# MAX6682_Breakout.net
KiCad netlist of a schematic drawn in EAGLE
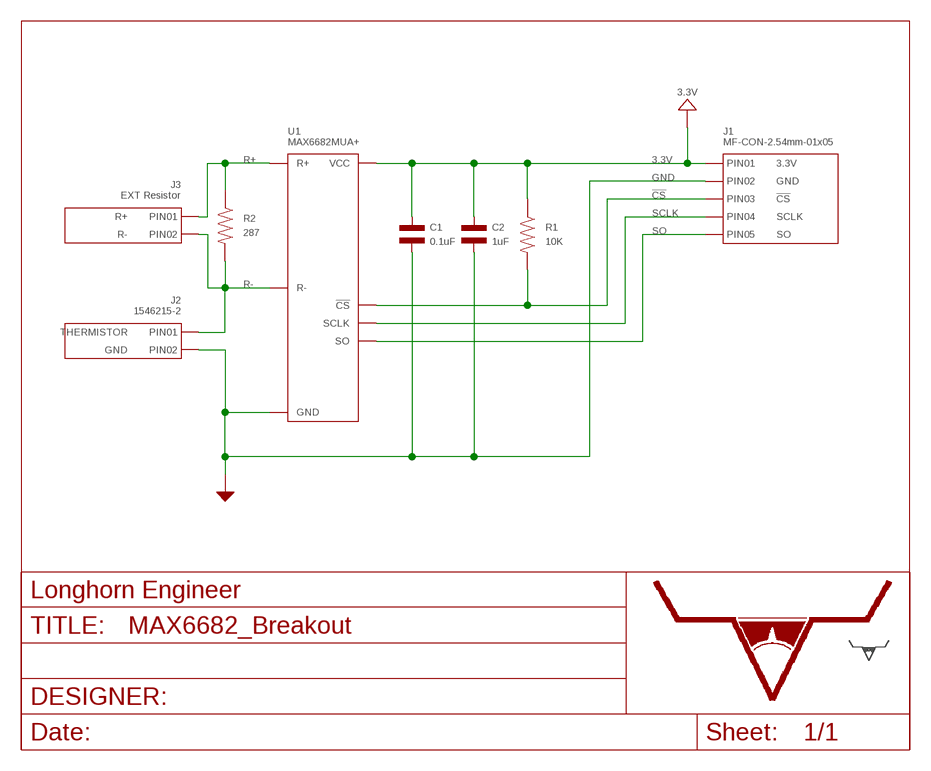
[diagram p0: schematic, sheet 1]

(export (version "E")
  (design (tool "Eeschema 10.0.6"))
  (components
    (comp (ref "C1")
      (value "0.1uF")
      (footprint "eagle-import:C0603")
      (libsource (lib "eagle-import") (part "CAPACITOR_NP_0603"))
    )
    (comp (ref "C2")
      (value "1uF")
      (footprint "eagle-import:C0603")
      (libsource (lib "eagle-import") (part "CAPACITOR_NP_0603"))
    )
    (comp (ref "J1")
      (value "MF-CON-2.54mm-01x05")
      (footprint "eagle-import:PTH_2.54MM_01X05")
      (fields
        (field (name "HOUSEPART") "YES")
        (field (name "LABEL01") "3.3V")
        (field (name "LABEL02") "GND")
        (field (name "LABEL03") "!CS")
        (field (name "LABEL04") "SCLK")
        (field (name "LABEL05") "SO")
      )
      (libsource (lib "eagle-import") (part "CON_01X05_PTH_2.54MM"))
    )
    (comp (ref "J2")
      (value "1546215-2")
      (footprint "eagle-import:1546215-2")
      (fields (field (name "LABEL01") "THERMISTOR") (field (name "LABEL02") "GND"))
      (libsource (lib "eagle-import") (part "CON_01X02_1546215-2"))
    )
    (comp (ref "J3")
      (value "EXT Resistor")
      (footprint "eagle-import:2.54MM_01X02_PIN_HEADER")
      (fields (field (name "LABEL01") "R+") (field (name "LABEL02") "R-"))
      (libsource (lib "eagle-import") (part "CON_01X02_2.54MM_PIN_HEADER"))
    )
    (comp (ref "R1")
      (value "10K")
      (footprint "eagle-import:R0603")
      (libsource (lib "eagle-import") (part "RESISTOR_0603"))
    )
    (comp (ref "R2")
      (value "287")
      (footprint "eagle-import:R0603")
      (fields (field (name "MPN") "ERA-3AEB2870V"))
      (libsource (lib "eagle-import") (part "RESISTOR_0603"))
    )
    (comp (ref "U$7")
      (value "LHE_FRAME")
      (footprint "eagle-import:LHE_FRAME")
      (fields (field (name "DNAME") "Parker Dillmann") (field (name "REVNUM") "REV: 1"))
      (libsource (lib "eagle-import") (part "LHE_FRAME"))
    )
    (comp (ref "U$8")
      (value "LHE_LOGOLHE_LOGO")
      (footprint "eagle-import:LHE_LOGO")
      (libsource (lib "eagle-import") (part "LHE_LOGOLHE_LOGO"))
    )
    (comp (ref "U1")
      (value "MAX6682MUA+")
      (footprint "eagle-import:MAX6682_UMAX-8")
      (libsource (lib "eagle-import") (part "MAX6682MUA+"))
    )
  )
  (nets
    (net (code "1") (name "/R+") (class "Default")
      (node (ref "J3") (pin "1") (pinfunction "PIN1_1") (pintype "bidirectional"))
      (node (ref "R2") (pin "P$1") (pinfunction "P$1_P$1") (pintype "passive"))
      (node (ref "U1") (pin "P$2") (pinfunction "R+_P$2") (pintype "bidirectional"))
    )
    (net (code "2") (name "/R-") (class "Default")
      (node (ref "J2") (pin "P$1") (pinfunction "PIN1_P$1") (pintype "bidirectional"))
      (node (ref "J3") (pin "2") (pinfunction "PIN2_2") (pintype "bidirectional"))
      (node (ref "R2") (pin "P$2") (pinfunction "P$2_P$2") (pintype "passive"))
      (node (ref "U1") (pin "P$3") (pinfunction "R-_P$3") (pintype "bidirectional"))
    )
    (net (code "3") (name "/SCLK") (class "Default")
      (node (ref "J1") (pin "P$4") (pinfunction "PIN4_P$4") (pintype "bidirectional"))
      (node (ref "U1") (pin "P$7") (pinfunction "SCLK_P$7") (pintype "bidirectional"))
    )
    (net (code "4") (name "/SO") (class "Default")
      (node (ref "J1") (pin "P$5") (pinfunction "PIN5_P$5") (pintype "bidirectional"))
      (node (ref "U1") (pin "P$6") (pinfunction "SO_P$6") (pintype "bidirectional"))
    )
    (net (code "5") (name "/~{CS}") (class "Default")
      (node (ref "J1") (pin "P$3") (pinfunction "PIN3_P$3") (pintype "bidirectional"))
      (node (ref "R1") (pin "P$2") (pinfunction "P$2_P$2") (pintype "passive"))
      (node (ref "U1") (pin "P$5") (pinfunction "~{CS}_P$5") (pintype "bidirectional"))
    )
    (net (code "6") (name "3.3V") (class "Default")
      (node (ref "C1") (pin "P$1") (pinfunction "P$1_P$1") (pintype "passive"))
      (node (ref "C2") (pin "P$1") (pinfunction "P$1_P$1") (pintype "passive"))
      (node (ref "J1") (pin "P$1") (pinfunction "PIN1_P$1") (pintype "bidirectional"))
      (node (ref "R1") (pin "P$1") (pinfunction "P$1_P$1") (pintype "passive"))
      (node (ref "U1") (pin "P$8") (pinfunction "VCC_P$8") (pintype "bidirectional"))
    )
    (net (code "7") (name "GND_RAIL") (class "Default")
      (node (ref "C1") (pin "P$2") (pinfunction "P$2_P$2") (pintype "passive"))
      (node (ref "C2") (pin "P$2") (pinfunction "P$2_P$2") (pintype "passive"))
      (node (ref "J1") (pin "P$2") (pinfunction "PIN2_P$2") (pintype "bidirectional"))
      (node (ref "J2") (pin "P$2") (pinfunction "PIN2_P$2") (pintype "bidirectional"))
      (node (ref "U1") (pin "P$4") (pinfunction "GND_P$4") (pintype "bidirectional"))
    )
  )
)
